# Bel_Pagar.net
KiCad netlist of a schematic drawn in EAGLE
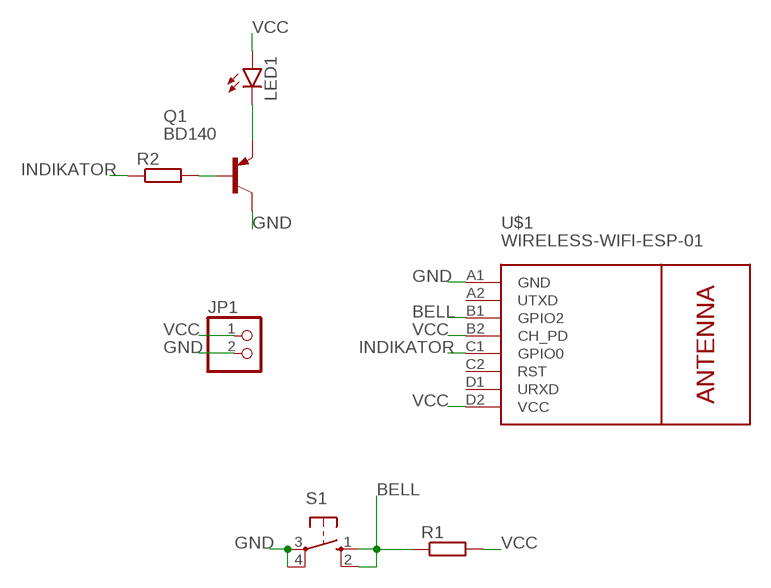
[diagram p0: schematic, sheet 1]

(export (version "E")
  (design (tool "Eeschema 10.0.6"))
  (components
    (comp (ref "JP1")
      (value "PINHD-1X2")
      (footprint "eagle-import:1X02")
      (libsource (lib "eagle-import") (part "PINHD-1X2"))
    )
    (comp (ref "LED1")
      (value "LED5MM")
      (footprint "eagle-import:LED5MM")
      (libsource (lib "eagle-import") (part "LED5MM"))
    )
    (comp (ref "Q1")
      (value "BD140")
      (footprint "eagle-import:TO126")
      (libsource (lib "eagle-import") (part "BD140"))
    )
    (comp (ref "R1")
      (value "R-EU_0207/10")
      (footprint "eagle-import:0207_10")
      (libsource (lib "eagle-import") (part "R-EU_0207/10"))
    )
    (comp (ref "R2")
      (value "R-EU_0207/10")
      (footprint "eagle-import:0207_10")
      (libsource (lib "eagle-import") (part "R-EU_0207/10"))
    )
    (comp (ref "S1")
      (value "10-XX")
      (footprint "eagle-import:B3F-10XX")
      (fields (field (name "MPN") "B3F-1000"))
      (libsource (lib "eagle-import") (part "10-XX"))
    )
    (comp (ref "U$1")
      (value "WIRELESS-WIFI-ESP-01")
      (footprint "eagle-import:WIRELESS-WIFI-ESP-01")
      (libsource (lib "eagle-import") (part "WIRELESS-WIFI-ESP-01"))
    )
  )
  (nets
    (net (code "1") (name "/BELL") (class "Default")
      (node (ref "R1") (pin "1") (pinfunction "1_1") (pintype "passive"))
      (node (ref "S1") (pin "1") (pinfunction "S_1") (pintype "passive"))
      (node (ref "S1") (pin "2") (pinfunction "S1_2") (pintype "passive"))
      (node (ref "U$1") (pin "B1") (pinfunction "GPIO2_B1") (pintype "bidirectional"))
    )
    (net (code "2") (name "/GND") (class "Default")
      (node (ref "JP1") (pin "2") (pinfunction "2_2") (pintype "passive"))
      (node (ref "Q1") (pin "2") (pinfunction "C_2") (pintype "passive"))
      (node (ref "S1") (pin "3") (pinfunction "P_3") (pintype "passive"))
      (node (ref "S1") (pin "4") (pinfunction "P1_4") (pintype "passive"))
      (node (ref "U$1") (pin "A1") (pinfunction "GND_A1") (pintype "power_in"))
    )
    (net (code "3") (name "/INDIKATOR") (class "Default")
      (node (ref "R2") (pin "1") (pinfunction "1_1") (pintype "passive"))
      (node (ref "U$1") (pin "C1") (pinfunction "GPIO0_C1") (pintype "bidirectional"))
    )
    (net (code "4") (name "/VCC") (class "Default")
      (node (ref "JP1") (pin "1") (pinfunction "1_1") (pintype "passive"))
      (node (ref "LED1") (pin "A") (pinfunction "A_A") (pintype "passive"))
      (node (ref "R1") (pin "2") (pinfunction "2_2") (pintype "passive"))
      (node (ref "U$1") (pin "B2") (pinfunction "CH_PD_B2") (pintype "bidirectional"))
      (node (ref "U$1") (pin "D2") (pinfunction "VCC_D2") (pintype "power_in"))
    )
    (net (code "5") (name "Net-(LED1-C)") (class "Default")
      (node (ref "LED1") (pin "K") (pinfunction "C_K") (pintype "passive"))
      (node (ref "Q1") (pin "1") (pinfunction "E_1") (pintype "passive"))
    )
    (net (code "6") (name "Net-(Q1-B)") (class "Default")
      (node (ref "Q1") (pin "3") (pinfunction "B_3") (pintype "passive"))
      (node (ref "R2") (pin "2") (pinfunction "2_2") (pintype "passive"))
    )
    (net (code "7") (name "unconnected-(U$1-RST-PadC2)") (class "Default")
      (node (ref "U$1") (pin "C2") (pinfunction "RST_C2") (pintype "bidirectional"))
    )
    (net (code "8") (name "unconnected-(U$1-URXD-PadD1)") (class "Default")
      (node (ref "U$1") (pin "D1") (pinfunction "URXD_D1") (pintype "bidirectional"))
    )
    (net (code "9") (name "unconnected-(U$1-UTXD-PadA2)") (class "Default")
      (node (ref "U$1") (pin "A2") (pinfunction "UTXD_A2") (pintype "bidirectional"))
    )
  )
)
